# 6e.net
KiCad netlist of a schematic drawn in EAGLE
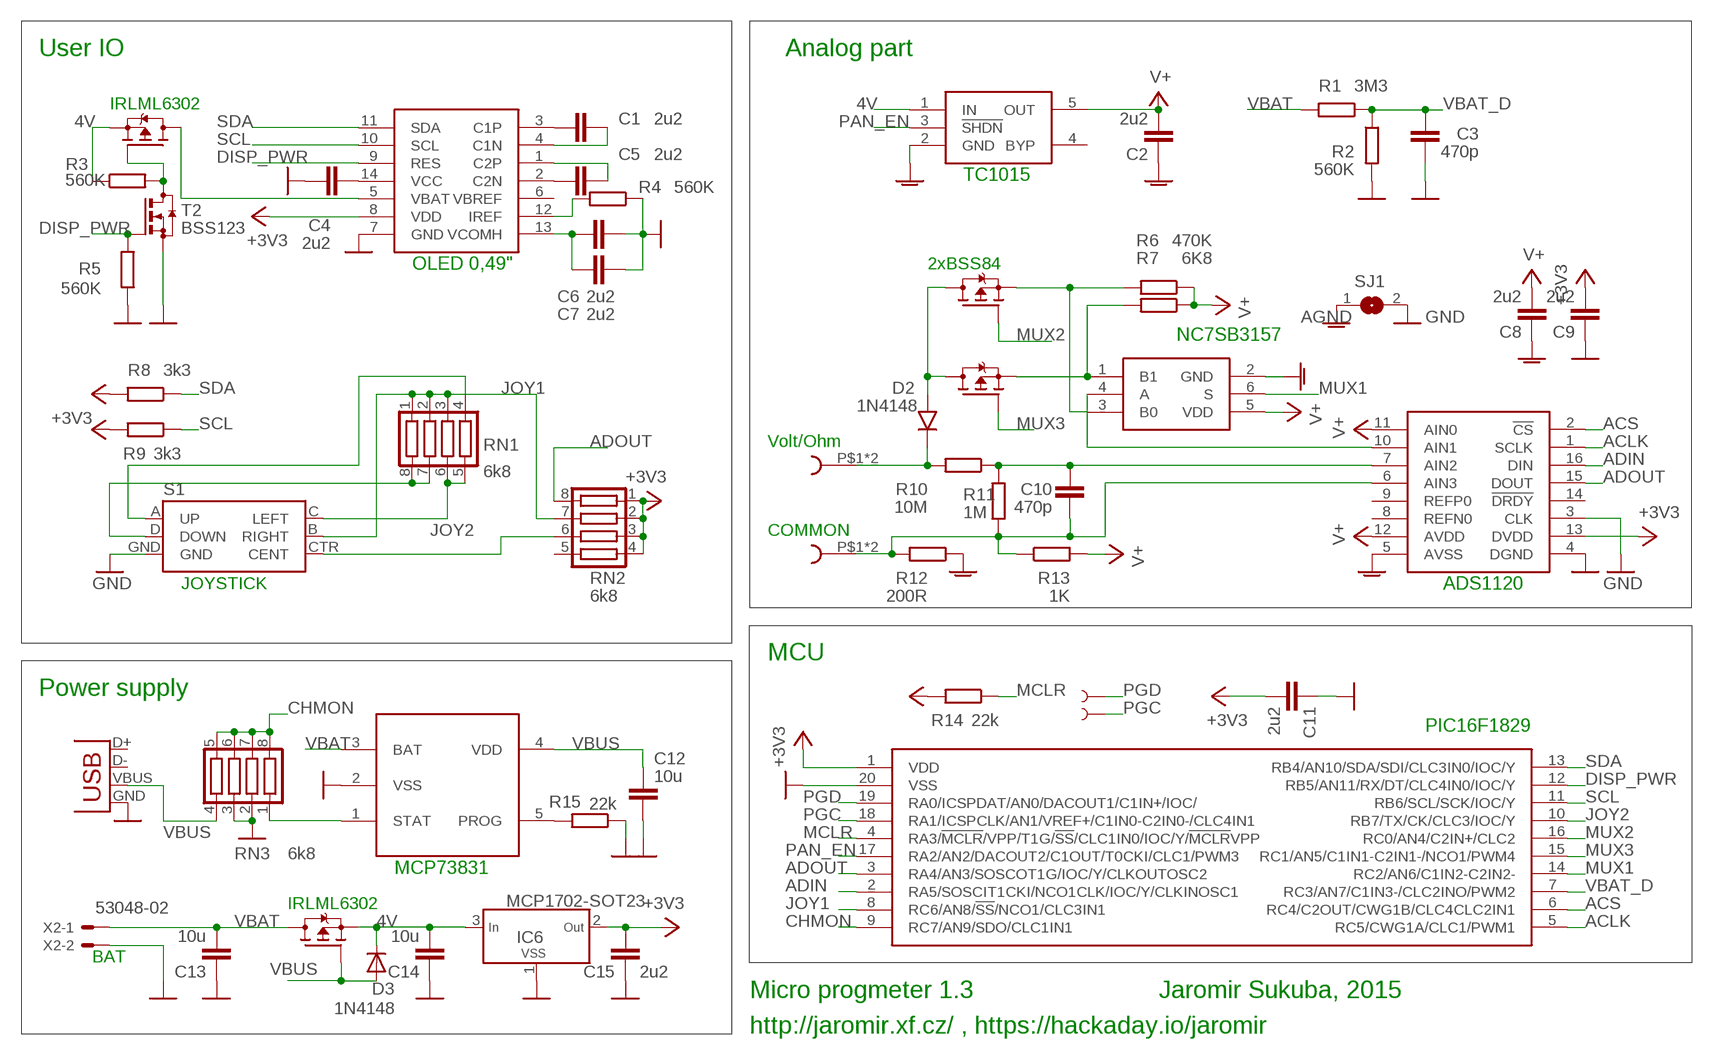
[diagram p0: schematic, sheet 1]

(export (version "E")
  (design (tool "Eeschema 10.0.6"))
  (components
    (comp (ref "C1")
      (value "2u2")
      (footprint "eagle-import:0603")
      (libsource (lib "eagle-import") (part "C_0603"))
    )
    (comp (ref "C2")
      (value "2u2")
      (footprint "eagle-import:0603")
      (libsource (lib "eagle-import") (part "C_0603"))
    )
    (comp (ref "C3")
      (value "470p")
      (footprint "eagle-import:0603")
      (libsource (lib "eagle-import") (part "C_0603"))
    )
    (comp (ref "C4")
      (value "2u2")
      (footprint "eagle-import:0603")
      (libsource (lib "eagle-import") (part "C_0603"))
    )
    (comp (ref "C5")
      (value "2u2")
      (footprint "eagle-import:0603")
      (libsource (lib "eagle-import") (part "C_0603"))
    )
    (comp (ref "C6")
      (value "2u2")
      (footprint "eagle-import:0603")
      (libsource (lib "eagle-import") (part "C_0603"))
    )
    (comp (ref "C7")
      (value "2u2")
      (footprint "eagle-import:0603")
      (libsource (lib "eagle-import") (part "C_0603"))
    )
    (comp (ref "C8")
      (value "2u2")
      (footprint "eagle-import:0603")
      (libsource (lib "eagle-import") (part "C_0603"))
    )
    (comp (ref "C9")
      (value "2u2")
      (footprint "eagle-import:0603")
      (libsource (lib "eagle-import") (part "C_0603"))
    )
    (comp (ref "C10")
      (value "470p")
      (footprint "eagle-import:0603")
      (libsource (lib "eagle-import") (part "C_0603"))
    )
    (comp (ref "C11")
      (value "2u2")
      (footprint "eagle-import:0603")
      (libsource (lib "eagle-import") (part "C_0603"))
    )
    (comp (ref "C12")
      (value "10u")
      (footprint "eagle-import:R0805")
      (libsource (lib "eagle-import") (part "C_0806"))
    )
    (comp (ref "C13")
      (value "10u")
      (footprint "eagle-import:R0805")
      (libsource (lib "eagle-import") (part "C_0806"))
    )
    (comp (ref "C14")
      (value "10u")
      (footprint "eagle-import:R0805")
      (libsource (lib "eagle-import") (part "C_0806"))
    )
    (comp (ref "C15")
      (value "2u2")
      (footprint "eagle-import:0603")
      (libsource (lib "eagle-import") (part "C_0603"))
    )
    (comp (ref "D1")
      (value "DISP_OLED_049B")
      (footprint "eagle-import:DISP_OLED_049_B")
      (libsource (lib "eagle-import") (part "DISP_OLED_049B"))
    )
    (comp (ref "D2")
      (value "1N4148")
      (footprint "eagle-import:SOD-80")
      (libsource (lib "eagle-import") (part "1N4148SOD"))
    )
    (comp (ref "D3")
      (value "1N4148")
      (footprint "eagle-import:SOD123")
      (libsource (lib "eagle-import") (part "DIODE-SOD123"))
    )
    (comp (ref "IC1")
      (value "TC1015")
      (footprint "eagle-import:SOT23-5")
      (libsource (lib "eagle-import") (part "TC1015"))
    )
    (comp (ref "IC2")
      (value "NC7SB3157")
      (footprint "eagle-import:SC70-6")
      (libsource (lib "eagle-import") (part "NC7SB3157"))
    )
    (comp (ref "IC3")
      (value "ADS1120")
      (footprint "eagle-import:TSSOP16")
      (libsource (lib "eagle-import") (part "ADS1120"))
    )
    (comp (ref "IC4")
      (value "MCP73831")
      (footprint "eagle-import:SOT23-5")
      (libsource (lib "eagle-import") (part "MCP73831"))
    )
    (comp (ref "IC5")
      (value "PIC16F1508SSOP20")
      (footprint "eagle-import:SSOP20")
      (libsource (lib "eagle-import") (part "PIC16F1508SSOP20"))
    )
    (comp (ref "IC6")
      (value "MCP1702-SOT23")
      (footprint "eagle-import:SOT23")
      (libsource (lib "eagle-import") (part "MCP1702-SOT23"))
    )
    (comp (ref "R1")
      (value "3M3")
      (footprint "eagle-import:0603")
      (libsource (lib "eagle-import") (part "R_0603"))
    )
    (comp (ref "R2")
      (value "560K")
      (footprint "eagle-import:0603")
      (libsource (lib "eagle-import") (part "R_0603"))
    )
    (comp (ref "R3")
      (value "560K")
      (footprint "eagle-import:0603")
      (libsource (lib "eagle-import") (part "R_0603"))
    )
    (comp (ref "R4")
      (value "560K")
      (footprint "eagle-import:0603")
      (libsource (lib "eagle-import") (part "R_0603"))
    )
    (comp (ref "R5")
      (value "560K")
      (footprint "eagle-import:0603")
      (libsource (lib "eagle-import") (part "R_0603"))
    )
    (comp (ref "R6")
      (value "470K")
      (footprint "eagle-import:R0805")
      (libsource (lib "eagle-import") (part "R_0805"))
    )
    (comp (ref "R7")
      (value "6K8")
      (footprint "eagle-import:R0805")
      (libsource (lib "eagle-import") (part "R_0805"))
    )
    (comp (ref "R8")
      (value "3k3")
      (footprint "eagle-import:0603")
      (libsource (lib "eagle-import") (part "R_0603"))
    )
    (comp (ref "R9")
      (value "3k3")
      (footprint "eagle-import:0603")
      (libsource (lib "eagle-import") (part "R_0603"))
    )
    (comp (ref "R10")
      (value "10M")
      (footprint "eagle-import:R0805")
      (libsource (lib "eagle-import") (part "R_0805"))
    )
    (comp (ref "R11")
      (value "1M")
      (footprint "eagle-import:R0805")
      (libsource (lib "eagle-import") (part "R_0805"))
    )
    (comp (ref "R12")
      (value "200R")
      (footprint "eagle-import:0603")
      (libsource (lib "eagle-import") (part "R_0603"))
    )
    (comp (ref "R13")
      (value "1K")
      (footprint "eagle-import:0603")
      (libsource (lib "eagle-import") (part "R_0603"))
    )
    (comp (ref "R14")
      (value "22k")
      (footprint "eagle-import:0603")
      (libsource (lib "eagle-import") (part "R_0603"))
    )
    (comp (ref "R15")
      (value "22k")
      (footprint "eagle-import:0603")
      (libsource (lib "eagle-import") (part "R_0603"))
    )
    (comp (ref "RN1")
      (value "6k8")
      (footprint "eagle-import:CTS742C083")
      (libsource (lib "eagle-import") (part "CTS742C083"))
    )
    (comp (ref "RN2")
      (value "6k8")
      (footprint "eagle-import:CTS742C083")
      (libsource (lib "eagle-import") (part "CTS742C083"))
    )
    (comp (ref "RN3")
      (value "6k8")
      (footprint "eagle-import:CTS742C083")
      (libsource (lib "eagle-import") (part "CTS742C083"))
    )
    (comp (ref "S1")
      (value "JOYSTICK_MINI")
      (footprint "eagle-import:JOYSTICK_MINI")
      (libsource (lib "eagle-import") (part "JOYSTICK_MINI"))
    )
    (comp (ref "SJ1") (value "SJ") (footprint "eagle-import:SJ") (libsource (lib "eagle-import") (part "SJ")))
    (comp (ref "T1")
      (value "BSS84")
      (footprint "eagle-import:SOT23-3")
      (libsource (lib "eagle-import") (part "BSS84"))
    )
    (comp (ref "T2")
      (value "BSS123")
      (footprint "eagle-import:SOT23")
      (libsource (lib "eagle-import") (part "BSS123"))
    )
    (comp (ref "T3")
      (value "BSS84")
      (footprint "eagle-import:SOT23-3")
      (libsource (lib "eagle-import") (part "BSS84"))
    )
    (comp (ref "T4")
      (value "BSS84")
      (footprint "eagle-import:SOT23-3")
      (libsource (lib "eagle-import") (part "BSS84"))
    )
    (comp (ref "T5")
      (value "BSS84")
      (footprint "eagle-import:SOT23-3")
      (libsource (lib "eagle-import") (part "BSS84"))
    )
    (comp (ref "TE1")
      (value "BANPLUG_2")
      (footprint "eagle-import:BANPLUG_2")
      (libsource (lib "eagle-import") (part "BANPLUG_2"))
    )
    (comp (ref "TE2")
      (value "BANPLUG_2")
      (footprint "eagle-import:BANPLUG_2")
      (libsource (lib "eagle-import") (part "BANPLUG_2"))
    )
    (comp (ref "TP1")
      (value "TEST-POINT3X5")
      (footprint "eagle-import:PAD.03X.05")
      (libsource (lib "eagle-import") (part "TEST-POINT3X5"))
    )
    (comp (ref "TP2")
      (value "TEST-POINT3X5")
      (footprint "eagle-import:PAD.03X.05")
      (libsource (lib "eagle-import") (part "TEST-POINT3X5"))
    )
    (comp (ref "X1")
      (value "USB-MICROB")
      (footprint "eagle-import:USB-MICROB")
      (libsource (lib "eagle-import") (part "USB-MICROB"))
    )
    (comp (ref "X2")
      (value "53048-02")
      (footprint "eagle-import:53048-02")
      (libsource (lib "eagle-import") (part "53?-02048"))
    )
  )
  (nets
    (net (code "1") (name "+3V3") (class "Default")
      (node (ref "C11") (pin "2") (pinfunction "2_2") (pintype "passive"))
      (node (ref "C15") (pin "2") (pinfunction "2_2") (pintype "passive"))
      (node (ref "C9") (pin "2") (pinfunction "2_2") (pintype "passive"))
      (node (ref "D1") (pin "8") (pinfunction "VDD_8") (pintype "bidirectional"))
      (node (ref "IC3") (pin "13") (pinfunction "DVDD_13") (pintype "bidirectional"))
      (node (ref "IC5") (pin "1") (pinfunction "VDD_1") (pintype "bidirectional"))
      (node (ref "IC6") (pin "2") (pinfunction "OUT_2") (pintype "output"))
      (node (ref "R14") (pin "2") (pinfunction "2_2") (pintype "passive"))
      (node (ref "R8") (pin "2") (pinfunction "2_2") (pintype "passive"))
      (node (ref "R9") (pin "2") (pinfunction "2_2") (pintype "passive"))
      (node (ref "RN2") (pin "1") (pinfunction "1_1") (pintype "passive"))
      (node (ref "RN2") (pin "2") (pinfunction "2_2") (pintype "passive"))
      (node (ref "RN2") (pin "3") (pinfunction "3_3") (pintype "passive"))
      (node (ref "RN2") (pin "4") (pinfunction "4_4") (pintype "passive"))
    )
    (net (code "2") (name "/4V") (class "Default")
      (node (ref "C14") (pin "2") (pinfunction "2_2") (pintype "passive"))
      (node (ref "D3") (pin "C") (pinfunction "C_C") (pintype "passive"))
      (node (ref "IC1") (pin "1") (pinfunction "IN_1") (pintype "bidirectional"))
      (node (ref "IC6") (pin "3") (pinfunction "IN_3") (pintype "input"))
      (node (ref "R3") (pin "1") (pinfunction "1_1") (pintype "passive"))
      (node (ref "T1") (pin "2") (pinfunction "S_2") (pintype "passive"))
      (node (ref "T5") (pin "2") (pinfunction "S_2") (pintype "passive"))
    )
    (net (code "3") (name "/ACLK") (class "Default")
      (node (ref "IC3") (pin "1") (pinfunction "SCLK_1") (pintype "bidirectional"))
      (node (ref "IC5") (pin "5") (pinfunction "RC5/CWG1A/CLC1/PWM1_5") (pintype "bidirectional"))
    )
    (net (code "4") (name "/ACS") (class "Default")
      (node (ref "IC3") (pin "2") (pinfunction "~{CS}_2") (pintype "bidirectional"))
      (node (ref "IC5") (pin "6") (pinfunction "RC4/C2OUT/CWG1B/CLC4CLC2IN1_6") (pintype "bidirectional"))
    )
    (net (code "5") (name "/ADIN") (class "Default")
      (node (ref "IC3") (pin "16") (pinfunction "DIN_16") (pintype "bidirectional"))
      (node (ref "IC5") (pin "2") (pinfunction "RA5/SOSCIT1CKI/NCO1CLK/IOC/Y/CLKINOSC1_2") (pintype "bidirectional"))
    )
    (net (code "6") (name "/ADOUT") (class "Default")
      (node (ref "IC3") (pin "15") (pinfunction "DOUT_15") (pintype "bidirectional"))
      (node (ref "IC5") (pin "3") (pinfunction "RA4/AN3/SOSCOT1G/IOC/Y/CLKOUTOSC2_3") (pintype "bidirectional"))
      (node (ref "RN2") (pin "8") (pinfunction "8_8") (pintype "passive"))
    )
    (net (code "7") (name "/CHMON") (class "Default")
      (node (ref "IC5") (pin "9") (pinfunction "RC7/AN9/SDO/CLC1IN1_9") (pintype "bidirectional"))
      (node (ref "RN3") (pin "5") (pinfunction "5_5") (pintype "passive"))
      (node (ref "RN3") (pin "6") (pinfunction "6_6") (pintype "passive"))
      (node (ref "RN3") (pin "7") (pinfunction "7_7") (pintype "passive"))
      (node (ref "RN3") (pin "8") (pinfunction "8_8") (pintype "passive"))
    )
    (net (code "8") (name "/DISP_PWR") (class "Default")
      (node (ref "D1") (pin "9") (pinfunction "RES_9") (pintype "bidirectional"))
      (node (ref "IC5") (pin "12") (pinfunction "RB5/AN11/RX/DT/CLC4IN0/IOC/Y_12") (pintype "bidirectional"))
      (node (ref "R5") (pin "2") (pinfunction "2_2") (pintype "passive"))
      (node (ref "T2") (pin "1") (pinfunction "G_1") (pintype "passive"))
    )
    (net (code "9") (name "/JOY1") (class "Default")
      (node (ref "IC5") (pin "8") (pinfunction "RC6/AN8/~{SS}/NCO1/CLC3IN1_8") (pintype "bidirectional"))
      (node (ref "RN1") (pin "1") (pinfunction "1_1") (pintype "passive"))
      (node (ref "RN1") (pin "2") (pinfunction "2_2") (pintype "passive"))
      (node (ref "RN1") (pin "3") (pinfunction "3_3") (pintype "passive"))
      (node (ref "RN2") (pin "7") (pinfunction "7_7") (pintype "passive"))
      (node (ref "S1") (pin "B") (pinfunction "RIGHT_B") (pintype "bidirectional"))
    )
    (net (code "10") (name "/JOY2") (class "Default")
      (node (ref "IC5") (pin "10") (pinfunction "RB7/TX/CK/CLC3/IOC/Y_10") (pintype "bidirectional"))
      (node (ref "RN2") (pin "6") (pinfunction "6_6") (pintype "passive"))
      (node (ref "S1") (pin "CTR") (pinfunction "CENT_CTR") (pintype "bidirectional"))
    )
    (net (code "11") (name "/MCLR") (class "Default")
      (node (ref "IC5") (pin "4") (pinfunction "RA3/~{MCLR}/VPP/T1G/~{SS}/CLC1IN0/IOC/Y/~{MCLR}VPP_4") (pintype "bidirectional"))
      (node (ref "R14") (pin "1") (pinfunction "1_1") (pintype "passive"))
    )
    (net (code "12") (name "/MUX1") (class "Default")
      (node (ref "IC2") (pin "6") (pinfunction "S_6") (pintype "bidirectional"))
      (node (ref "IC5") (pin "14") (pinfunction "RC2/AN6/C1IN2-C2IN2-_14") (pintype "bidirectional"))
    )
    (net (code "13") (name "/MUX2") (class "Default")
      (node (ref "IC5") (pin "16") (pinfunction "RC0/AN4/C2IN+/CLC2_16") (pintype "bidirectional"))
      (node (ref "T3") (pin "1") (pinfunction "G_1") (pintype "passive"))
    )
    (net (code "14") (name "/MUX3") (class "Default")
      (node (ref "IC5") (pin "15") (pinfunction "RC1/AN5/C1IN1-C2IN1-/NCO1/PWM4_15") (pintype "bidirectional"))
      (node (ref "T4") (pin "1") (pinfunction "G_1") (pintype "passive"))
    )
    (net (code "15") (name "/PAN_EN") (class "Default")
      (node (ref "IC1") (pin "3") (pinfunction "~{SHDN}_3") (pintype "bidirectional"))
      (node (ref "IC5") (pin "17") (pinfunction "RA2/AN2/DACOUT2/C1OUT/T0CKI/CLC1/PWM3_17") (pintype "bidirectional"))
    )
    (net (code "16") (name "/PGC") (class "Default")
      (node (ref "IC5") (pin "18") (pinfunction "RA1/ICSPCLK/AN1/VREF+/C1IN0-C2IN0-/CLC4IN1_18") (pintype "bidirectional"))
      (node (ref "TP2") (pin "P$1") (pinfunction "1_P$1") (pintype "bidirectional"))
    )
    (net (code "17") (name "/PGD") (class "Default")
      (node (ref "IC5") (pin "19") (pinfunction "RA0/ICSPDAT/AN0/DACOUT1/C1IN+/IOC/_19") (pintype "bidirectional"))
      (node (ref "TP1") (pin "P$1") (pinfunction "1_P$1") (pintype "bidirectional"))
    )
    (net (code "18") (name "/SCL") (class "Default")
      (node (ref "D1") (pin "10") (pinfunction "SCL_10") (pintype "bidirectional"))
      (node (ref "IC5") (pin "11") (pinfunction "RB6/SCL/SCK/IOC/Y_11") (pintype "bidirectional"))
      (node (ref "R9") (pin "1") (pinfunction "1_1") (pintype "passive"))
    )
    (net (code "19") (name "/SDA") (class "Default")
      (node (ref "D1") (pin "11") (pinfunction "SDA_11") (pintype "bidirectional"))
      (node (ref "IC5") (pin "13") (pinfunction "RB4/AN10/SDA/SDI/CLC3IN0/IOC/Y_13") (pintype "bidirectional"))
      (node (ref "R8") (pin "1") (pinfunction "1_1") (pintype "passive"))
    )
    (net (code "20") (name "/VBAT") (class "Default")
      (node (ref "C13") (pin "2") (pinfunction "2_2") (pintype "passive"))
      (node (ref "IC4") (pin "3") (pinfunction "BAT_3") (pintype "bidirectional"))
      (node (ref "R1") (pin "2") (pinfunction "2_2") (pintype "passive"))
      (node (ref "T5") (pin "3") (pinfunction "D_3") (pintype "passive"))
      (node (ref "X2") (pin "1") (pinfunction "S_1") (pintype "passive"))
    )
    (net (code "21") (name "/VBAT_D") (class "Default")
      (node (ref "C3") (pin "2") (pinfunction "2_2") (pintype "passive"))
      (node (ref "IC5") (pin "7") (pinfunction "RC3/AN7/C1IN3-/CLC2INO/PWM2_7") (pintype "bidirectional"))
      (node (ref "R1") (pin "1") (pinfunction "1_1") (pintype "passive"))
      (node (ref "R2") (pin "1") (pinfunction "1_1") (pintype "passive"))
    )
    (net (code "22") (name "/VBUS") (class "Default")
      (node (ref "C12") (pin "1") (pinfunction "1_1") (pintype "passive"))
      (node (ref "D3") (pin "A") (pinfunction "A_A") (pintype "passive"))
      (node (ref "IC4") (pin "4") (pinfunction "VDD_4") (pintype "bidirectional"))
      (node (ref "RN3") (pin "4") (pinfunction "4_4") (pintype "passive"))
      (node (ref "T5") (pin "1") (pinfunction "G_1") (pintype "passive"))
      (node (ref "X1") (pin "VBUS") (pinfunction "VBUS_VBUS") (pintype "bidirectional"))
    )
    (net (code "23") (name "AGND") (class "Default")
      (node (ref "C2") (pin "1") (pinfunction "1_1") (pintype "passive"))
      (node (ref "C8") (pin "1") (pinfunction "1_1") (pintype "passive"))
      (node (ref "IC1") (pin "2") (pinfunction "GND_2") (pintype "bidirectional"))
      (node (ref "IC2") (pin "2") (pinfunction "GND_2") (pintype "bidirectional"))
      (node (ref "IC3") (pin "5") (pinfunction "AVSS_5") (pintype "bidirectional"))
      (node (ref "R12") (pin "1") (pinfunction "1_1") (pintype "passive"))
      (node (ref "SJ1") (pin "1") (pinfunction "1_1") (pintype "passive"))
    )
    (net (code "24") (name "GND") (class "Default")
      (node (ref "C11") (pin "1") (pinfunction "1_1") (pintype "passive"))
      (node (ref "C12") (pin "2") (pinfunction "2_2") (pintype "passive"))
      (node (ref "C13") (pin "1") (pinfunction "1_1") (pintype "passive"))
      (node (ref "C14") (pin "1") (pinfunction "1_1") (pintype "passive"))
      (node (ref "C15") (pin "1") (pinfunction "1_1") (pintype "passive"))
      (node (ref "C3") (pin "1") (pinfunction "1_1") (pintype "passive"))
      (node (ref "C4") (pin "1") (pinfunction "1_1") (pintype "passive"))
      (node (ref "C6") (pin "2") (pinfunction "2_2") (pintype "passive"))
      (node (ref "C7") (pin "2") (pinfunction "2_2") (pintype "passive"))
      (node (ref "C9") (pin "1") (pinfunction "1_1") (pintype "passive"))
      (node (ref "D1") (pin "7") (pinfunction "GND_7") (pintype "bidirectional"))
      (node (ref "IC3") (pin "3") (pinfunction "CLK_3") (pintype "bidirectional"))
      (node (ref "IC3") (pin "4") (pinfunction "DGND_4") (pintype "bidirectional"))
      (node (ref "IC4") (pin "2") (pinfunction "VSS_2") (pintype "bidirectional"))
      (node (ref "IC5") (pin "20") (pinfunction "VSS_20") (pintype "bidirectional"))
      (node (ref "IC6") (pin "1") (pinfunction "VSS_1") (pintype "input"))
      (node (ref "R15") (pin "1") (pinfunction "1_1") (pintype "passive"))
      (node (ref "R2") (pin "2") (pinfunction "2_2") (pintype "passive"))
      (node (ref "R4") (pin "1") (pinfunction "1_1") (pintype "passive"))
      (node (ref "R5") (pin "1") (pinfunction "1_1") (pintype "passive"))
      (node (ref "RN3") (pin "2") (pinfunction "2_2") (pintype "passive"))
      (node (ref "RN3") (pin "3") (pinfunction "3_3") (pintype "passive"))
      (node (ref "S1") (pin "GND") (pinfunction "GND_GND") (pintype "bidirectional"))
      (node (ref "SJ1") (pin "2") (pinfunction "2_2") (pintype "passive"))
      (node (ref "T2") (pin "2") (pinfunction "S_2") (pintype "passive"))
      (node (ref "X1") (pin "GND") (pinfunction "GND_GND") (pintype "bidirectional"))
      (node (ref "X2") (pin "2") (pinfunction "S_2") (pintype "passive"))
    )
    (net (code "25") (name "Net-(D1-C1N)") (class "Default")
      (node (ref "C1") (pin "2") (pinfunction "2_2") (pintype "passive"))
      (node (ref "D1") (pin "4") (pinfunction "C1N_4") (pintype "bidirectional"))
    )
    (net (code "26") (name "Net-(D1-C1P)") (class "Default")
      (node (ref "C1") (pin "1") (pinfunction "1_1") (pintype "passive"))
      (node (ref "D1") (pin "3") (pinfunction "C1P_3") (pintype "bidirectional"))
    )
    (net (code "27") (name "Net-(D1-C2N)") (class "Default")
      (node (ref "C5") (pin "1") (pinfunction "1_1") (pintype "passive"))
      (node (ref "D1") (pin "2") (pinfunction "C2N_2") (pintype "bidirectional"))
    )
    (net (code "28") (name "Net-(D1-C2P)") (class "Default")
      (node (ref "C5") (pin "2") (pinfunction "2_2") (pintype "passive"))
      (node (ref "D1") (pin "1") (pinfunction "C2P_1") (pintype "bidirectional"))
    )
    (net (code "29") (name "Net-(D1-IREF)") (class "Default")
      (node (ref "D1") (pin "12") (pinfunction "IREF_12") (pintype "bidirectional"))
      (node (ref "R4") (pin "2") (pinfunction "2_2") (pintype "passive"))
    )
    (net (code "30") (name "Net-(D1-VBAT)") (class "Default")
      (node (ref "D1") (pin "5") (pinfunction "VBAT_5") (pintype "bidirectional"))
      (node (ref "T1") (pin "3") (pinfunction "D_3") (pintype "passive"))
    )
    (net (code "31") (name "Net-(D1-VCC)") (class "Default")
      (node (ref "C4") (pin "2") (pinfunction "2_2") (pintype "passive"))
      (node (ref "D1") (pin "14") (pinfunction "VCC_14") (pintype "bidirectional"))
    )
    (net (code "32") (name "Net-(D1-VCOMH)") (class "Default")
      (node (ref "C6") (pin "1") (pinfunction "1_1") (pintype "passive"))
      (node (ref "C7") (pin "1") (pinfunction "1_1") (pintype "passive"))
      (node (ref "D1") (pin "13") (pinfunction "VCOMH_13") (pintype "bidirectional"))
    )
    (net (code "33") (name "Net-(D2-PadK)") (class "Default")
      (node (ref "D2") (pin "K") (pinfunction "K_K") (pintype "output"))
      (node (ref "R10") (pin "2") (pinfunction "2_2") (pintype "passive"))
      (node (ref "TE1") (pin "P$1") (pinfunction "P$1_P$1") (pintype "bidirectional"))
      (node (ref "TE1") (pin "P$2") (pinfunction "P$1_P$2") (pintype "bidirectional"))
    )
    (net (code "34") (name "Net-(IC2-A)") (class "Default")
      (node (ref "IC2") (pin "4") (pinfunction "A_4") (pintype "bidirectional"))
      (node (ref "IC3") (pin "10") (pinfunction "AIN1_10") (pintype "bidirectional"))
    )
    (net (code "35") (name "Net-(IC2-B0)") (class "Default")
      (node (ref "IC2") (pin "3") (pinfunction "B0_3") (pintype "bidirectional"))
      (node (ref "R6") (pin "2") (pinfunction "2_2") (pintype "passive"))
      (node (ref "T3") (pin "2") (pinfunction "S_2") (pintype "passive"))
    )
    (net (code "36") (name "Net-(IC2-B1)") (class "Default")
      (node (ref "IC2") (pin "1") (pinfunction "B1_1") (pintype "bidirectional"))
      (node (ref "R7") (pin "2") (pinfunction "2_2") (pintype "passive"))
      (node (ref "T4") (pin "2") (pinfunction "S_2") (pintype "passive"))
    )
    (net (code "37") (name "Net-(IC3-AIN2)") (class "Default")
      (node (ref "C10") (pin "2") (pinfunction "2_2") (pintype "passive"))
      (node (ref "IC3") (pin "7") (pinfunction "AIN2_7") (pintype "bidirectional"))
      (node (ref "R10") (pin "1") (pinfunction "1_1") (pintype "passive"))
      (node (ref "R11") (pin "1") (pinfunction "1_1") (pintype "passive"))
    )
    (net (code "38") (name "Net-(IC3-AIN3)") (class "Default")
      (node (ref "C10") (pin "1") (pinfunction "1_1") (pintype "passive"))
      (node (ref "IC3") (pin "6") (pinfunction "AIN3_6") (pintype "bidirectional"))
      (node (ref "R11") (pin "2") (pinfunction "2_2") (pintype "passive"))
      (node (ref "R12") (pin "2") (pinfunction "2_2") (pintype "passive"))
      (node (ref "R13") (pin "1") (pinfunction "1_1") (pintype "passive"))
      (node (ref "TE2") (pin "P$1") (pinfunction "P$1_P$1") (pintype "bidirectional"))
      (node (ref "TE2") (pin "P$2") (pinfunction "P$1_P$2") (pintype "bidirectional"))
    )
    (net (code "39") (name "Net-(IC4-PROG)") (class "Default")
      (node (ref "IC4") (pin "5") (pinfunction "PROG_5") (pintype "bidirectional"))
      (node (ref "R15") (pin "2") (pinfunction "2_2") (pintype "passive"))
    )
    (net (code "40") (name "Net-(IC4-STAT)") (class "Default")
      (node (ref "IC4") (pin "1") (pinfunction "STAT_1") (pintype "bidirectional"))
      (node (ref "RN3") (pin "1") (pinfunction "1_1") (pintype "passive"))
    )
    (net (code "41") (name "Net-(S1-DOWN)") (class "Default")
      (node (ref "RN1") (pin "7") (pinfunction "7_7") (pintype "passive"))
      (node (ref "RN1") (pin "8") (pinfunction "8_8") (pintype "passive"))
      (node (ref "S1") (pin "D") (pinfunction "DOWN_D") (pintype "bidirectional"))
    )
    (net (code "42") (name "Net-(S1-LEFT)") (class "Default")
      (node (ref "RN1") (pin "5") (pinfunction "5_5") (pintype "passive"))
      (node (ref "RN1") (pin "6") (pinfunction "6_6") (pintype "passive"))
      (node (ref "S1") (pin "C") (pinfunction "LEFT_C") (pintype "bidirectional"))
    )
    (net (code "43") (name "Net-(S1-UP)") (class "Default")
      (node (ref "RN1") (pin "4") (pinfunction "4_4") (pintype "passive"))
      (node (ref "S1") (pin "A") (pinfunction "UP_A") (pintype "bidirectional"))
    )
    (net (code "44") (name "Net-(T1-G)") (class "Default")
      (node (ref "R3") (pin "2") (pinfunction "2_2") (pintype "passive"))
      (node (ref "T1") (pin "1") (pinfunction "G_1") (pintype "passive"))
      (node (ref "T2") (pin "3") (pinfunction "D_3") (pintype "passive"))
    )
    (net (code "45") (name "Net-(T3-D)") (class "Default")
      (node (ref "D2") (pin "A") (pinfunction "A_A") (pintype "input"))
      (node (ref "T3") (pin "3") (pinfunction "D_3") (pintype "passive"))
      (node (ref "T4") (pin "3") (pinfunction "D_3") (pintype "passive"))
    )
    (net (code "46") (name "V+") (class "Default")
      (node (ref "C2") (pin "2") (pinfunction "2_2") (pintype "passive"))
      (node (ref "C8") (pin "2") (pinfunction "2_2") (pintype "passive"))
      (node (ref "IC1") (pin "5") (pinfunction "OUT_5") (pintype "bidirectional"))
      (node (ref "IC2") (pin "5") (pinfunction "VDD_5") (pintype "bidirectional"))
      (node (ref "IC3") (pin "11") (pinfunction "AIN0_11") (pintype "bidirectional"))
      (node (ref "IC3") (pin "12") (pinfunction "AVDD_12") (pintype "bidirectional"))
      (node (ref "R13") (pin "2") (pinfunction "2_2") (pintype "passive"))
      (node (ref "R6") (pin "1") (pinfunction "1_1") (pintype "passive"))
      (node (ref "R7") (pin "1") (pinfunction "1_1") (pintype "passive"))
    )
    (net (code "47") (name "unconnected-(D1-VBREF-Pad6)") (class "Default")
      (node (ref "D1") (pin "6") (pinfunction "VBREF_6") (pintype "bidirectional"))
    )
    (net (code "48") (name "unconnected-(IC1-BYP-Pad4)") (class "Default")
      (node (ref "IC1") (pin "4") (pinfunction "BYP_4") (pintype "bidirectional"))
    )
    (net (code "49") (name "unconnected-(IC3-REFN0-Pad8)") (class "Default")
      (node (ref "IC3") (pin "8") (pinfunction "REFN0_8") (pintype "bidirectional"))
    )
    (net (code "50") (name "unconnected-(IC3-REFP0-Pad9)") (class "Default")
      (node (ref "IC3") (pin "9") (pinfunction "REFP0_9") (pintype "bidirectional"))
    )
    (net (code "51") (name "unconnected-(IC3-~{DRDY}-Pad14)") (class "Default")
      (node (ref "IC3") (pin "14") (pinfunction "~{DRDY}_14") (pintype "bidirectional"))
    )
    (net (code "52") (name "unconnected-(RN2-Pad5)") (class "Default")
      (node (ref "RN2") (pin "5") (pinfunction "5_5") (pintype "passive"))
    )
    (net (code "53") (name "unconnected-(X1-PadD+)") (class "Default")
      (node (ref "X1") (pin "D+") (pinfunction "D+_D+") (pintype "bidirectional"))
    )
    (net (code "54") (name "unconnected-(X1-PadD-)") (class "Default")
      (node (ref "X1") (pin "D-") (pinfunction "D-_D-") (pintype "bidirectional"))
    )
  )
)
